# USB_Bit_Whacker-18F2553.net
KiCad netlist of a schematic drawn in EAGLE
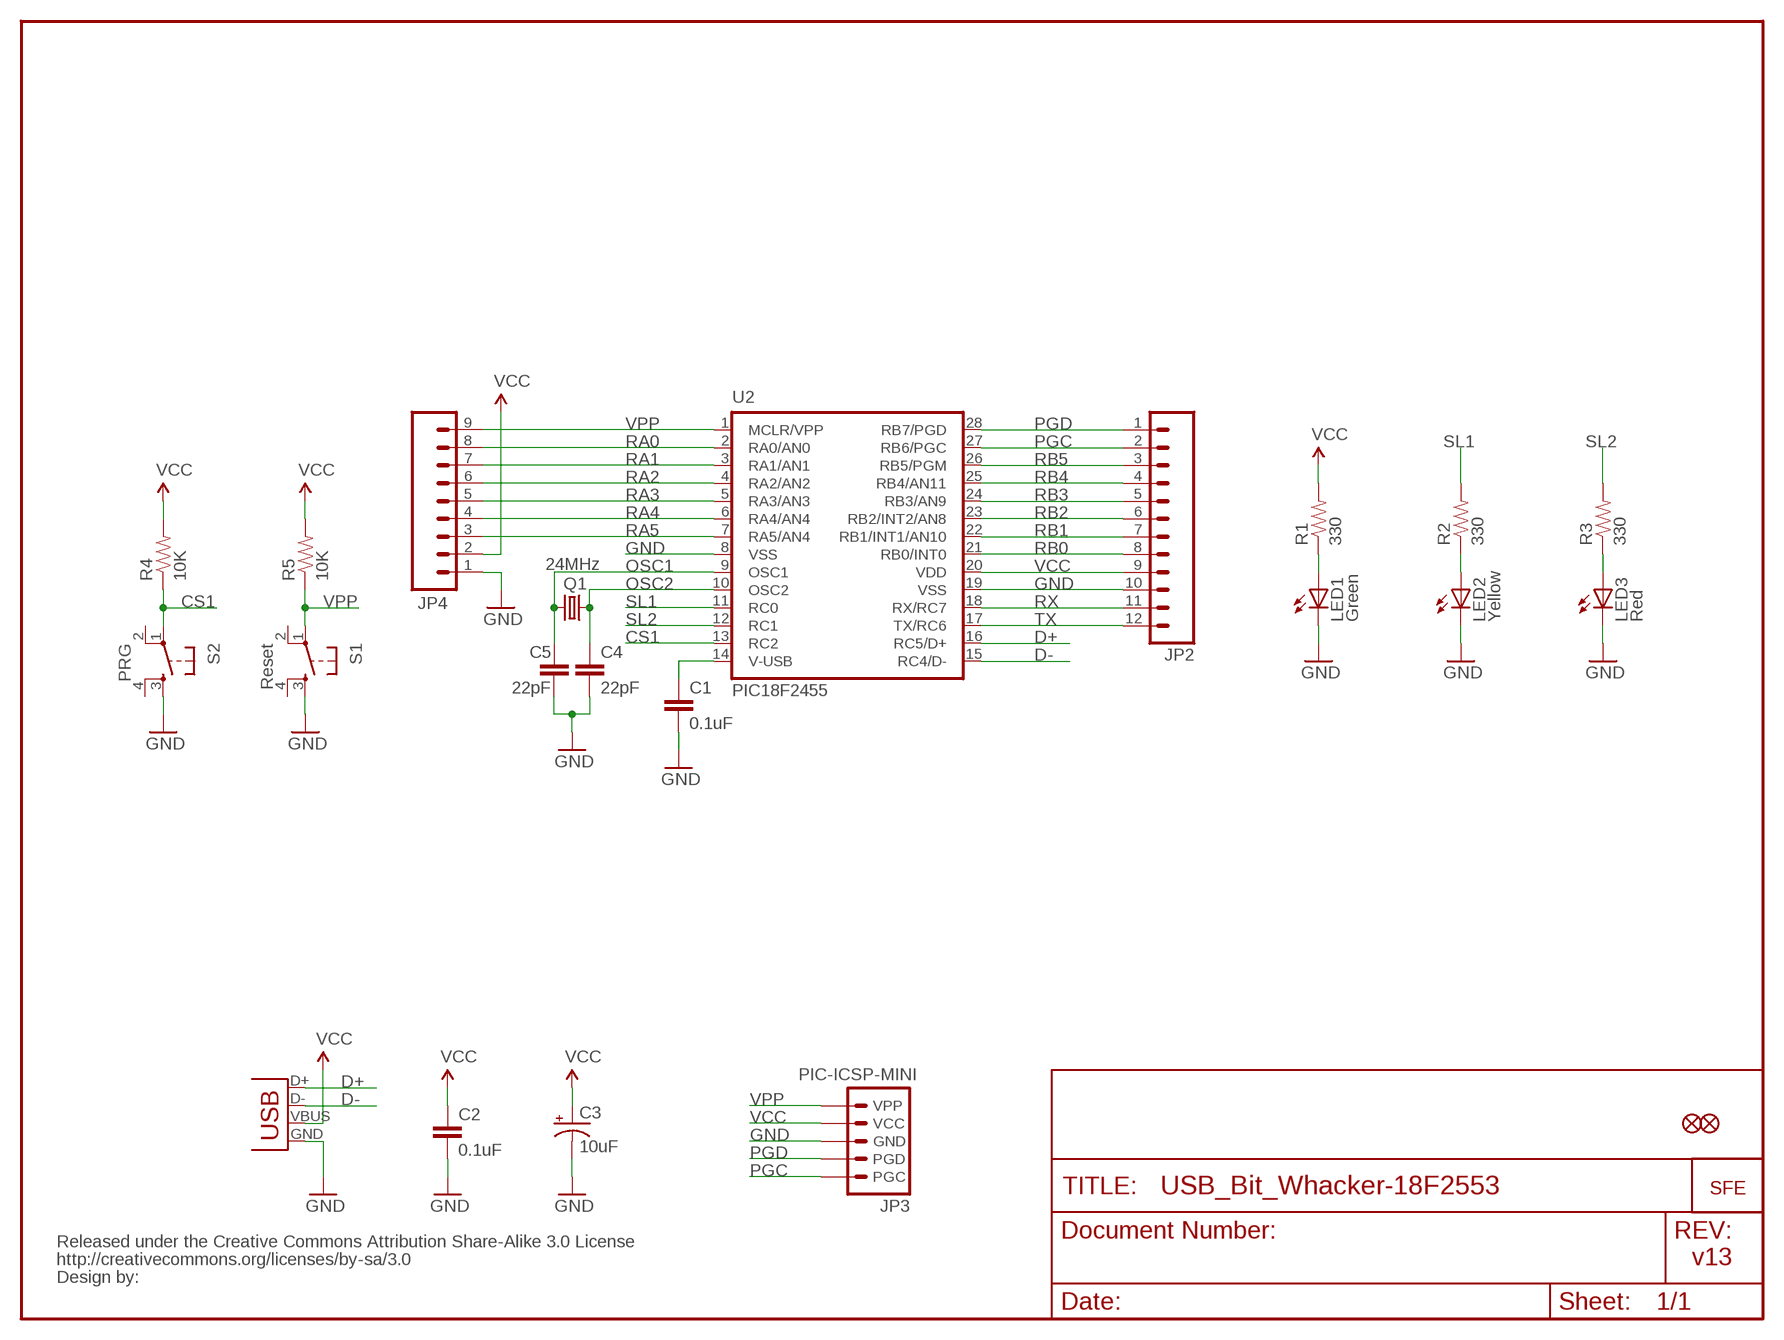
[diagram p0: schematic, sheet 1]

(export (version "E")
  (design (tool "Eeschema 10.0.6"))
  (components
    (comp (ref "C1")
      (value "0.1uF")
      (footprint "eagle-import:0402-CAP")
      (libsource (lib "eagle-import") (part "CAP0402-CAP"))
    )
    (comp (ref "C2")
      (value "0.1uF")
      (footprint "eagle-import:0402-CAP")
      (libsource (lib "eagle-import") (part "CAP0402-CAP"))
    )
    (comp (ref "C3")
      (value "10uF")
      (footprint "eagle-import:EIA3216")
      (libsource (lib "eagle-import") (part "CAP_POL1206"))
    )
    (comp (ref "C4")
      (value "22pF")
      (footprint "eagle-import:0402-CAP")
      (libsource (lib "eagle-import") (part "CAP0402-CAP"))
    )
    (comp (ref "C5")
      (value "22pF")
      (footprint "eagle-import:0402-CAP")
      (libsource (lib "eagle-import") (part "CAP0402-CAP"))
    )
    (comp (ref "FID1")
      (value "FIDUCIAL1X2")
      (footprint "eagle-import:FIDUCIAL-1X2")
      (libsource (lib "eagle-import") (part "FIDUCIAL1X2"))
    )
    (comp (ref "FID2")
      (value "FIDUCIAL1X2")
      (footprint "eagle-import:FIDUCIAL-1X2")
      (libsource (lib "eagle-import") (part "FIDUCIAL1X2"))
    )
    (comp (ref "JP2")
      (value "M12PTH")
      (footprint "eagle-import:1X12")
      (libsource (lib "eagle-import") (part "M12PTH"))
    )
    (comp (ref "JP3")
      (value "PIC-ICSP-MINI")
      (footprint "eagle-import:PIC-ICSP-MINI")
      (libsource (lib "eagle-import") (part "PIC-ICSP-MINI"))
    )
    (comp (ref "JP4")
      (value "M09")
      (footprint "eagle-import:1X09")
      (libsource (lib "eagle-import") (part "M09"))
    )
    (comp (ref "LED1")
      (value "Green")
      (footprint "eagle-import:LED-1206")
      (libsource (lib "eagle-import") (part "LED1206"))
    )
    (comp (ref "LED2")
      (value "Yellow")
      (footprint "eagle-import:LED-1206")
      (libsource (lib "eagle-import") (part "LED1206"))
    )
    (comp (ref "LED3")
      (value "Red")
      (footprint "eagle-import:LED-1206")
      (libsource (lib "eagle-import") (part "LED1206"))
    )
    (comp (ref "Q1")
      (value "24MHz")
      (footprint "eagle-import:CRYSTAL-SMD-5X3")
      (libsource (lib "eagle-import") (part "CRYSTAL5X3"))
    )
    (comp (ref "R1")
      (value "330")
      (footprint "eagle-import:0402-RES")
      (libsource (lib "eagle-import") (part "RESISTOR0402-RES"))
    )
    (comp (ref "R2")
      (value "330")
      (footprint "eagle-import:0402-RES")
      (libsource (lib "eagle-import") (part "RESISTOR0402-RES"))
    )
    (comp (ref "R3")
      (value "330")
      (footprint "eagle-import:0402-RES")
      (libsource (lib "eagle-import") (part "RESISTOR0402-RES"))
    )
    (comp (ref "R4")
      (value "10K")
      (footprint "eagle-import:0402-RES")
      (libsource (lib "eagle-import") (part "RESISTOR0402-RES"))
    )
    (comp (ref "R5")
      (value "10K")
      (footprint "eagle-import:0402-RES")
      (libsource (lib "eagle-import") (part "RESISTOR0402-RES"))
    )
    (comp (ref "S1")
      (value "Reset")
      (footprint "eagle-import:TACTILE_SWITCH_SMD")
      (libsource (lib "eagle-import") (part "TAC_SWITCHSMD"))
    )
    (comp (ref "S2")
      (value "PRG")
      (footprint "eagle-import:TACTILE_SWITCH_SMD")
      (libsource (lib "eagle-import") (part "TAC_SWITCHSMD"))
    )
    (comp (ref "U$1")
      (value "LOGO-SFENEW")
      (footprint "eagle-import:SFE-NEW-WEBLOGO")
      (libsource (lib "eagle-import") (part "LOGO-SFENEW"))
    )
    (comp (ref "U$2")
      (value "CREATIVE_COMMONS")
      (footprint "eagle-import:CREATIVE_COMMONS")
      (libsource (lib "eagle-import") (part "CREATIVE_COMMONS"))
    )
    (comp (ref "U2")
      (value "PIC18F2455")
      (footprint "eagle-import:SO-28W")
      (libsource (lib "eagle-import") (part "PIC18F2455SMD"))
    )
    (comp (ref "X1")
      (value "USBSMD")
      (footprint "eagle-import:USB-MINIB")
      (libsource (lib "eagle-import") (part "USBSMD"))
    )
  )
  (nets
    (net (code "1") (name "/CS1") (class "Default")
      (node (ref "R4") (pin "1") (pinfunction "1_1") (pintype "passive"))
      (node (ref "S2") (pin "1") (pinfunction "1_1") (pintype "passive"))
      (node (ref "U2") (pin "13") (pinfunction "RC2_13") (pintype "bidirectional"))
    )
    (net (code "2") (name "/D+") (class "Default")
      (node (ref "U2") (pin "16") (pinfunction "RC5/D+_16") (pintype "bidirectional"))
      (node (ref "X1") (pin "D+") (pinfunction "D+_D+") (pintype "bidirectional"))
    )
    (net (code "3") (name "/D-") (class "Default")
      (node (ref "U2") (pin "15") (pinfunction "RC4/D-_15") (pintype "bidirectional"))
      (node (ref "X1") (pin "D-") (pinfunction "D-_D-") (pintype "bidirectional"))
    )
    (net (code "4") (name "/OSC1") (class "Default")
      (node (ref "C5") (pin "1") (pinfunction "1_1") (pintype "passive"))
      (node (ref "Q1") (pin "3") (pinfunction "2_3") (pintype "passive"))
      (node (ref "U2") (pin "9") (pinfunction "OSC1_9") (pintype "bidirectional"))
    )
    (net (code "5") (name "/OSC2") (class "Default")
      (node (ref "C4") (pin "1") (pinfunction "1_1") (pintype "passive"))
      (node (ref "Q1") (pin "1") (pinfunction "1_1") (pintype "passive"))
      (node (ref "U2") (pin "10") (pinfunction "OSC2_10") (pintype "bidirectional"))
    )
    (net (code "6") (name "/PGC") (class "Default")
      (node (ref "JP2") (pin "2") (pinfunction "2_2") (pintype "passive"))
      (node (ref "JP3") (pin "5") (pinfunction "PGC_5") (pintype "passive"))
      (node (ref "U2") (pin "27") (pinfunction "RB6/PGC_27") (pintype "bidirectional"))
    )
    (net (code "7") (name "/PGD") (class "Default")
      (node (ref "JP2") (pin "1") (pinfunction "1_1") (pintype "passive"))
      (node (ref "JP3") (pin "4") (pinfunction "PGD_4") (pintype "passive"))
      (node (ref "U2") (pin "28") (pinfunction "RB7/PGD_28") (pintype "bidirectional"))
    )
    (net (code "8") (name "/RA0") (class "Default")
      (node (ref "JP4") (pin "8") (pinfunction "8_8") (pintype "passive"))
      (node (ref "U2") (pin "2") (pinfunction "RA0/AN0_2") (pintype "bidirectional"))
    )
    (net (code "9") (name "/RA1") (class "Default")
      (node (ref "JP4") (pin "7") (pinfunction "7_7") (pintype "passive"))
      (node (ref "U2") (pin "3") (pinfunction "RA1/AN1_3") (pintype "bidirectional"))
    )
    (net (code "10") (name "/RA2") (class "Default")
      (node (ref "JP4") (pin "6") (pinfunction "6_6") (pintype "passive"))
      (node (ref "U2") (pin "4") (pinfunction "RA2/AN2_4") (pintype "bidirectional"))
    )
    (net (code "11") (name "/RA3") (class "Default")
      (node (ref "JP4") (pin "5") (pinfunction "5_5") (pintype "passive"))
      (node (ref "U2") (pin "5") (pinfunction "RA3/AN3_5") (pintype "bidirectional"))
    )
    (net (code "12") (name "/RA4") (class "Default")
      (node (ref "JP4") (pin "4") (pinfunction "4_4") (pintype "passive"))
      (node (ref "U2") (pin "6") (pinfunction "RA4/AN4_6") (pintype "bidirectional"))
    )
    (net (code "13") (name "/RA5") (class "Default")
      (node (ref "JP4") (pin "3") (pinfunction "3_3") (pintype "passive"))
      (node (ref "U2") (pin "7") (pinfunction "RA5/AN4_7") (pintype "bidirectional"))
    )
    (net (code "14") (name "/RB0") (class "Default")
      (node (ref "JP2") (pin "8") (pinfunction "8_8") (pintype "passive"))
      (node (ref "U2") (pin "21") (pinfunction "RB0/INT0_21") (pintype "bidirectional"))
    )
    (net (code "15") (name "/RB1") (class "Default")
      (node (ref "JP2") (pin "7") (pinfunction "7_7") (pintype "passive"))
      (node (ref "U2") (pin "22") (pinfunction "RB1/INT1/AN10_22") (pintype "bidirectional"))
    )
    (net (code "16") (name "/RB2") (class "Default")
      (node (ref "JP2") (pin "6") (pinfunction "6_6") (pintype "passive"))
      (node (ref "U2") (pin "23") (pinfunction "RB2/INT2/AN8_23") (pintype "bidirectional"))
    )
    (net (code "17") (name "/RB3") (class "Default")
      (node (ref "JP2") (pin "5") (pinfunction "5_5") (pintype "passive"))
      (node (ref "U2") (pin "24") (pinfunction "RB3/AN9_24") (pintype "bidirectional"))
    )
    (net (code "18") (name "/RB4") (class "Default")
      (node (ref "JP2") (pin "4") (pinfunction "4_4") (pintype "passive"))
      (node (ref "U2") (pin "25") (pinfunction "RB4/AN11_25") (pintype "bidirectional"))
    )
    (net (code "19") (name "/RB5") (class "Default")
      (node (ref "JP2") (pin "3") (pinfunction "3_3") (pintype "passive"))
      (node (ref "U2") (pin "26") (pinfunction "RB5/PGM_26") (pintype "bidirectional"))
    )
    (net (code "20") (name "/RX") (class "Default")
      (node (ref "JP2") (pin "11") (pinfunction "11_11") (pintype "passive"))
      (node (ref "U2") (pin "18") (pinfunction "RX/RC7_18") (pintype "input"))
    )
    (net (code "21") (name "/SL1") (class "Default")
      (node (ref "R2") (pin "2") (pinfunction "2_2") (pintype "passive"))
      (node (ref "U2") (pin "11") (pinfunction "RC0_11") (pintype "bidirectional"))
    )
    (net (code "22") (name "/SL2") (class "Default")
      (node (ref "R3") (pin "2") (pinfunction "2_2") (pintype "passive"))
      (node (ref "U2") (pin "12") (pinfunction "RC1_12") (pintype "bidirectional"))
    )
    (net (code "23") (name "/TX") (class "Default")
      (node (ref "JP2") (pin "12") (pinfunction "12_12") (pintype "passive"))
      (node (ref "U2") (pin "17") (pinfunction "TX/RC6_17") (pintype "bidirectional"))
    )
    (net (code "24") (name "/VPP") (class "Default")
      (node (ref "JP3") (pin "1") (pinfunction "VPP_1") (pintype "passive"))
      (node (ref "JP4") (pin "9") (pinfunction "9_9") (pintype "passive"))
      (node (ref "R5") (pin "1") (pinfunction "1_1") (pintype "passive"))
      (node (ref "S1") (pin "1") (pinfunction "1_1") (pintype "passive"))
      (node (ref "U2") (pin "1") (pinfunction "MCLR/VPP_1") (pintype "bidirectional"))
    )
    (net (code "25") (name "GND") (class "Default")
      (node (ref "C1") (pin "2") (pinfunction "2_2") (pintype "passive"))
      (node (ref "C2") (pin "2") (pinfunction "2_2") (pintype "passive"))
      (node (ref "C3") (pin "C") (pinfunction "-_C") (pintype "passive"))
      (node (ref "C4") (pin "2") (pinfunction "2_2") (pintype "passive"))
      (node (ref "C5") (pin "2") (pinfunction "2_2") (pintype "passive"))
      (node (ref "JP2") (pin "10") (pinfunction "10_10") (pintype "passive"))
      (node (ref "JP3") (pin "3") (pinfunction "GND_3") (pintype "passive"))
      (node (ref "JP4") (pin "1") (pinfunction "1_1") (pintype "passive"))
      (node (ref "LED1") (pin "C") (pinfunction "C_C") (pintype "passive"))
      (node (ref "LED2") (pin "C") (pinfunction "C_C") (pintype "passive"))
      (node (ref "LED3") (pin "C") (pinfunction "C_C") (pintype "passive"))
      (node (ref "S1") (pin "3") (pinfunction "3_3") (pintype "passive"))
      (node (ref "S2") (pin "3") (pinfunction "3_3") (pintype "passive"))
      (node (ref "U2") (pin "19") (pinfunction "VSS_19") (pintype "power_in"))
      (node (ref "U2") (pin "8") (pinfunction "VSS_8") (pintype "power_in"))
      (node (ref "X1") (pin "GND") (pinfunction "GND_GND") (pintype "bidirectional"))
    )
    (net (code "26") (name "Net-(LED1-PadA)") (class "Default")
      (node (ref "LED1") (pin "A") (pinfunction "A_A") (pintype "passive"))
      (node (ref "R1") (pin "1") (pinfunction "1_1") (pintype "passive"))
    )
    (net (code "27") (name "Net-(LED2-PadA)") (class "Default")
      (node (ref "LED2") (pin "A") (pinfunction "A_A") (pintype "passive"))
      (node (ref "R2") (pin "1") (pinfunction "1_1") (pintype "passive"))
    )
    (net (code "28") (name "Net-(LED3-PadA)") (class "Default")
      (node (ref "LED3") (pin "A") (pinfunction "A_A") (pintype "passive"))
      (node (ref "R3") (pin "1") (pinfunction "1_1") (pintype "passive"))
    )
    (net (code "29") (name "Net-(U2-V-USB)") (class "Default")
      (node (ref "C1") (pin "1") (pinfunction "1_1") (pintype "passive"))
      (node (ref "U2") (pin "14") (pinfunction "V-USB_14") (pintype "bidirectional"))
    )
    (net (code "30") (name "VCC") (class "Default")
      (node (ref "C2") (pin "1") (pinfunction "1_1") (pintype "passive"))
      (node (ref "C3") (pin "A") (pinfunction "+_A") (pintype "passive"))
      (node (ref "JP2") (pin "9") (pinfunction "9_9") (pintype "passive"))
      (node (ref "JP3") (pin "2") (pinfunction "VCC_2") (pintype "passive"))
      (node (ref "JP4") (pin "2") (pinfunction "2_2") (pintype "passive"))
      (node (ref "R1") (pin "2") (pinfunction "2_2") (pintype "passive"))
      (node (ref "R4") (pin "2") (pinfunction "2_2") (pintype "passive"))
      (node (ref "R5") (pin "2") (pinfunction "2_2") (pintype "passive"))
      (node (ref "U2") (pin "20") (pinfunction "VDD_20") (pintype "power_in"))
      (node (ref "X1") (pin "VBUS") (pinfunction "VBUS_VBUS") (pintype "bidirectional"))
    )
    (net (code "31") (name "unconnected-(S1-Pad2)") (class "Default")
      (node (ref "S1") (pin "2") (pinfunction "2_2") (pintype "passive"))
    )
    (net (code "32") (name "unconnected-(S1-Pad4)") (class "Default")
      (node (ref "S1") (pin "4") (pinfunction "4_4") (pintype "passive"))
    )
    (net (code "33") (name "unconnected-(S2-Pad2)") (class "Default")
      (node (ref "S2") (pin "2") (pinfunction "2_2") (pintype "passive"))
    )
    (net (code "34") (name "unconnected-(S2-Pad4)") (class "Default")
      (node (ref "S2") (pin "4") (pinfunction "4_4") (pintype "passive"))
    )
  )
)
